# debugging_board_3_KEY1.net
KiCad netlist of a schematic drawn in Altium Designer
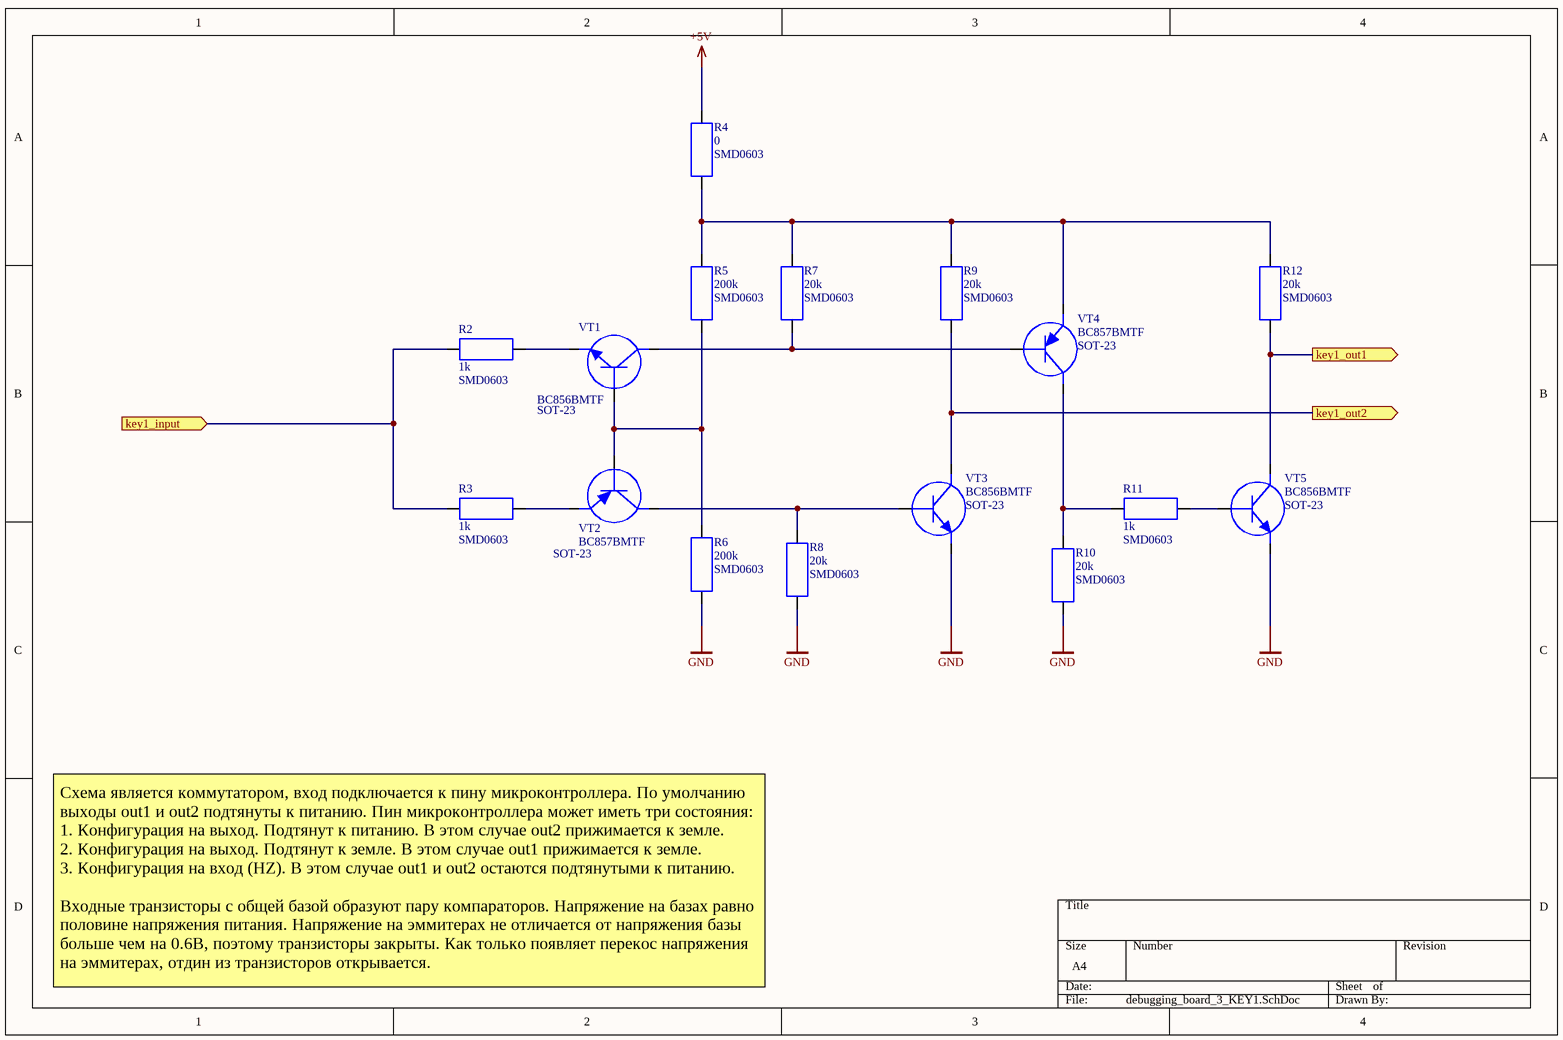
[diagram p0: debugging_board_3_KEY1.SchDoc]

(export (version "E")
  (design (tool "Eeschema 10.0.6"))
  (components
    (comp (ref "R2")
      (value "1k")
      (footprint "SMD0603(1005)")
      (fields (field (name "PACKAGE") "SMD0603"))
      (libsource (lib "MechanikLibrary") (part "R_0603"))
    )
    (comp (ref "R3")
      (value "1k")
      (footprint "SMD0603(1005)")
      (fields (field (name "PACKAGE") "SMD0603"))
      (libsource (lib "MechanikLibrary") (part "R_0603"))
    )
    (comp (ref "R4")
      (value "0")
      (footprint "SMD0603(1005)")
      (fields (field (name "PACKAGE") "SMD0603"))
      (libsource (lib "MechanikLibrary") (part "R_0603"))
    )
    (comp (ref "R5")
      (value "200k")
      (footprint "SMD0603(1005)")
      (fields (field (name "PACKAGE") "SMD0603"))
      (libsource (lib "MechanikLibrary") (part "R_0603"))
    )
    (comp (ref "R6")
      (value "200k")
      (footprint "SMD0603(1005)")
      (fields (field (name "PACKAGE") "SMD0603"))
      (libsource (lib "MechanikLibrary") (part "R_0603"))
    )
    (comp (ref "R7")
      (value "20k")
      (footprint "SMD0603(1005)")
      (fields (field (name "PACKAGE") "SMD0603"))
      (libsource (lib "MechanikLibrary") (part "R_0603"))
    )
    (comp (ref "R8")
      (value "20k")
      (footprint "SMD0603(1005)")
      (fields (field (name "PACKAGE") "SMD0603"))
      (libsource (lib "MechanikLibrary") (part "R_0603"))
    )
    (comp (ref "R9")
      (value "20k")
      (footprint "SMD0603(1005)")
      (fields (field (name "PACKAGE") "SMD0603"))
      (libsource (lib "MechanikLibrary") (part "R_0603"))
    )
    (comp (ref "R10")
      (value "20k")
      (footprint "SMD0603(1005)")
      (fields (field (name "PACKAGE") "SMD0603"))
      (libsource (lib "MechanikLibrary") (part "R_0603"))
    )
    (comp (ref "R11")
      (value "1k")
      (footprint "SMD0603(1005)")
      (fields (field (name "PACKAGE") "SMD0603"))
      (libsource (lib "MechanikLibrary") (part "R_0603"))
    )
    (comp (ref "R12")
      (value "20k")
      (footprint "SMD0603(1005)")
      (fields (field (name "PACKAGE") "SMD0603"))
      (libsource (lib "MechanikLibrary") (part "R_0603"))
    )
    (comp (ref "VT1")
      (value "BC856BMTF")
      (footprint "SOT23-3")
      (fields (field (name "PACKAGE") "SOT-23"))
      (libsource (lib "MechanikLibrary") (part "VT_NPN_SOT23_3"))
    )
    (comp (ref "VT2")
      (value "BC857BMTF")
      (footprint "SOT23-3")
      (fields (field (name "PACKAGE") "SOT-23"))
      (libsource (lib "MechanikLibrary") (part "VT_PNP_SOT23_3"))
    )
    (comp (ref "VT3")
      (value "BC856BMTF")
      (footprint "SOT23-3")
      (fields (field (name "PACKAGE") "SOT-23"))
      (libsource (lib "MechanikLibrary") (part "VT_NPN_SOT23_3"))
    )
    (comp (ref "VT4")
      (value "BC857BMTF")
      (footprint "SOT23-3")
      (fields (field (name "PACKAGE") "SOT-23"))
      (libsource (lib "MechanikLibrary") (part "VT_PNP_SOT23_3"))
    )
    (comp (ref "VT5")
      (value "BC856BMTF")
      (footprint "SOT23-3")
      (fields (field (name "PACKAGE") "SOT-23"))
      (libsource (lib "MechanikLibrary") (part "VT_NPN_SOT23_3"))
    )
  )
  (nets
    (net (code "1") (name "+5V") (class "Default") (node (ref "R4") (pin "1") (pintype "passive")))
    (net (code "2") (name "/key1_input") (class "Default")
      (node (ref "R2") (pin "2") (pintype "passive"))
      (node (ref "R3") (pin "2") (pintype "passive"))
    )
    (net (code "3") (name "/key1_out1") (class "Default")
      (node (ref "R12") (pin "2") (pintype "passive"))
      (node (ref "VT5") (pin "3") (pintype "passive"))
    )
    (net (code "4") (name "/key1_out2") (class "Default")
      (node (ref "R9") (pin "2") (pintype "passive"))
      (node (ref "VT3") (pin "3") (pintype "passive"))
    )
    (net (code "5") (name "GND") (class "Default")
      (node (ref "R10") (pin "2") (pintype "passive"))
      (node (ref "R6") (pin "2") (pintype "passive"))
      (node (ref "R8") (pin "2") (pintype "passive"))
      (node (ref "VT3") (pin "2") (pintype "passive"))
      (node (ref "VT5") (pin "2") (pintype "passive"))
    )
    (net (code "6") (name "Net-(R2-Pad1)") (class "Default")
      (node (ref "R2") (pin "1") (pintype "passive"))
      (node (ref "VT1") (pin "2") (pintype "passive"))
    )
    (net (code "7") (name "Net-(R3-Pad1)") (class "Default")
      (node (ref "R3") (pin "1") (pintype "passive"))
      (node (ref "VT2") (pin "2") (pintype "passive"))
    )
    (net (code "8") (name "Net-(R5-Pad2)") (class "Default")
      (node (ref "R5") (pin "2") (pintype "passive"))
      (node (ref "R6") (pin "1") (pintype "passive"))
      (node (ref "VT1") (pin "1") (pintype "passive"))
      (node (ref "VT2") (pin "1") (pintype "passive"))
    )
    (net (code "9") (name "Net-(R7-Pad2)") (class "Default")
      (node (ref "R7") (pin "2") (pintype "passive"))
      (node (ref "VT1") (pin "3") (pintype "passive"))
      (node (ref "VT4") (pin "1") (pintype "passive"))
    )
    (net (code "10") (name "Net-(R8-Pad1)") (class "Default")
      (node (ref "R8") (pin "1") (pintype "passive"))
      (node (ref "VT2") (pin "3") (pintype "passive"))
      (node (ref "VT3") (pin "1") (pintype "passive"))
    )
    (net (code "11") (name "Net-(R10-Pad1)") (class "Default")
      (node (ref "R10") (pin "1") (pintype "passive"))
      (node (ref "R11") (pin "2") (pintype "passive"))
      (node (ref "VT4") (pin "3") (pintype "passive"))
    )
    (net (code "12") (name "Net-(R11-Pad1)") (class "Default")
      (node (ref "R11") (pin "1") (pintype "passive"))
      (node (ref "VT5") (pin "1") (pintype "passive"))
    )
    (net (code "13") (name "Net-(R12-Pad1)") (class "Default")
      (node (ref "R12") (pin "1") (pintype "passive"))
      (node (ref "R4") (pin "2") (pintype "passive"))
      (node (ref "R5") (pin "1") (pintype "passive"))
      (node (ref "R7") (pin "1") (pintype "passive"))
      (node (ref "R9") (pin "1") (pintype "passive"))
      (node (ref "VT4") (pin "2") (pintype "passive"))
    )
  )
)
